# brains.net
KiCad netlist of a schematic drawn in EAGLE
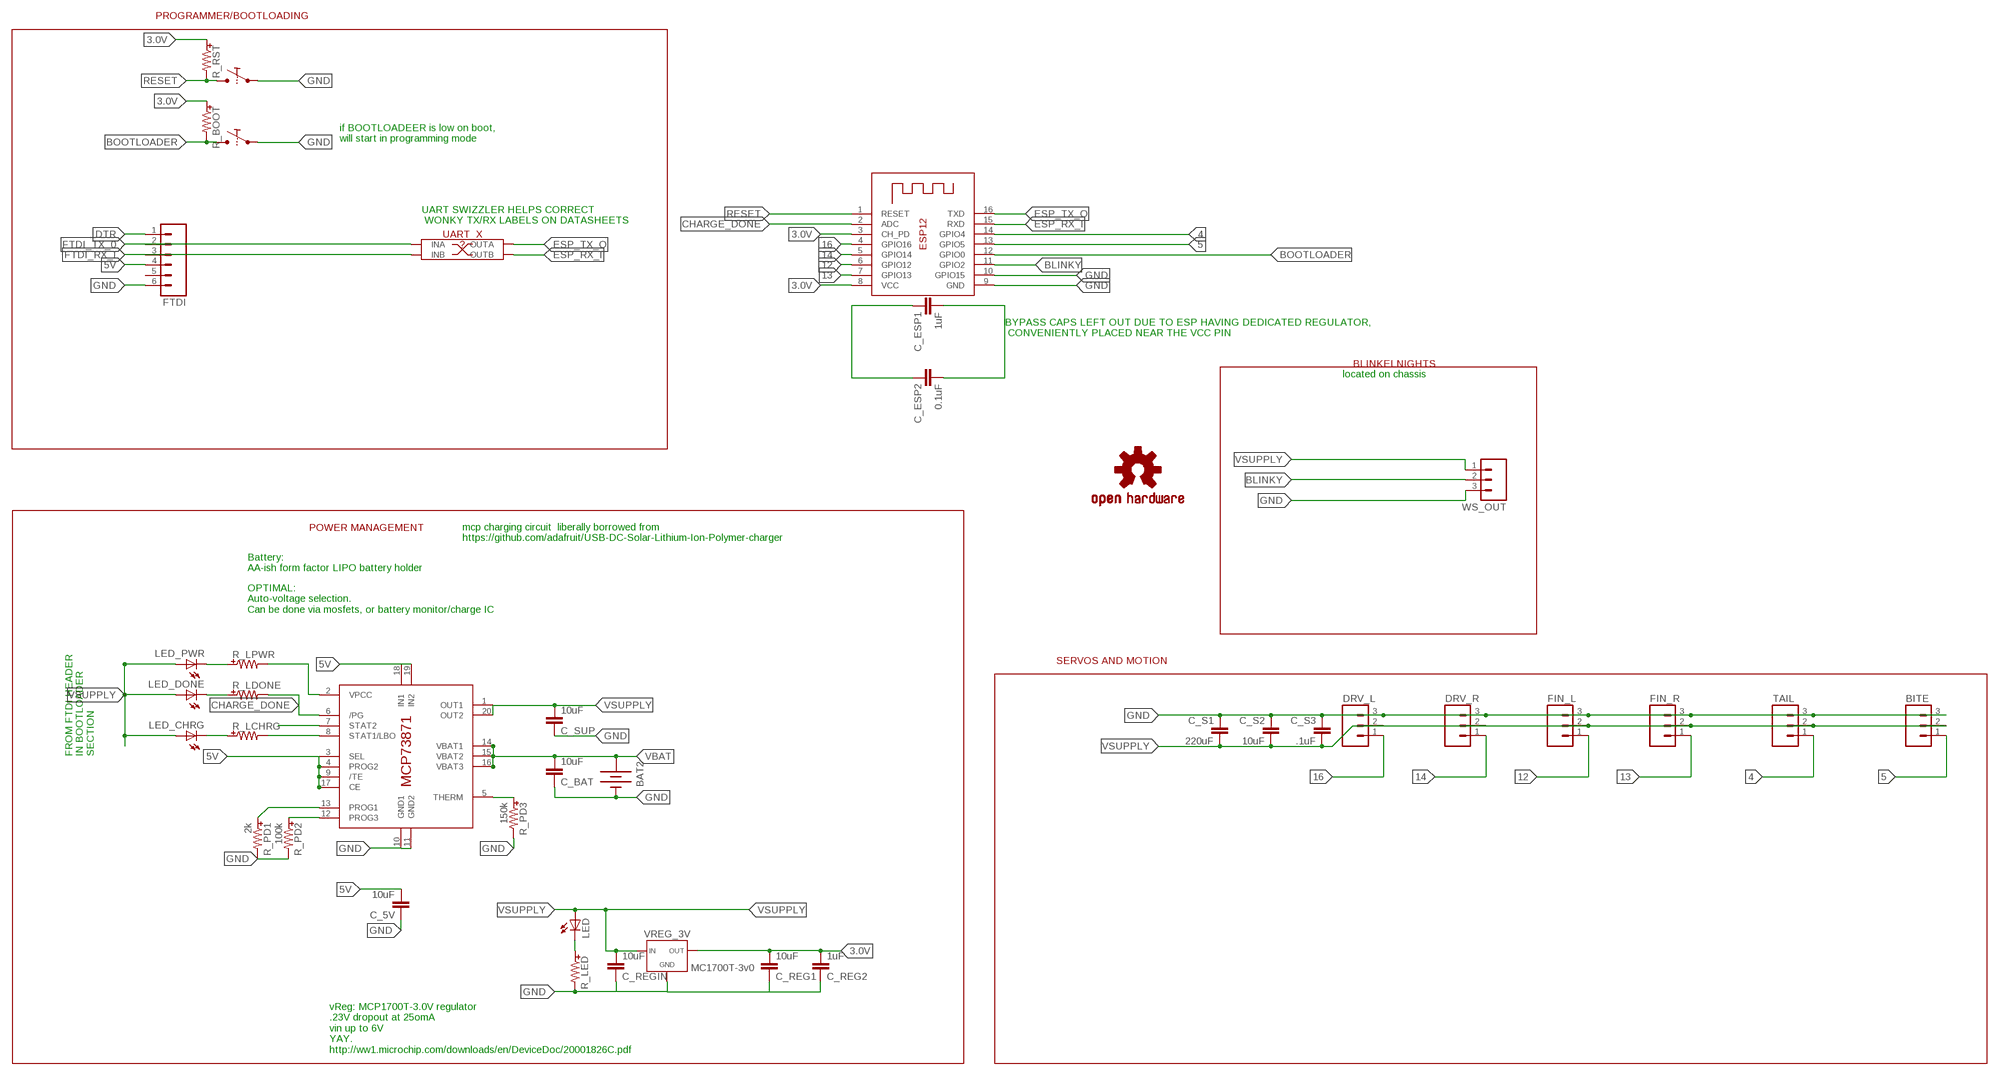
[diagram p0: schematic, sheet 1]

(export (version "E")
  (design (tool "Eeschema 10.0.6"))
  (components
    (comp (ref "BAT2")
      (value "BATTERYAA")
      (footprint "eagle-import:BATTERY-AA")
      (libsource (lib "eagle-import") (part "BATTERYAA"))
    )
    (comp (ref "BITE")
      (value "M03LOCK")
      (footprint "eagle-import:1X03_LOCK")
      (libsource (lib "eagle-import") (part "M03LOCK"))
    )
    (comp (ref "BTN_PROG")
      (value "BUTTONPJRC")
      (footprint "eagle-import:BUTTON-PJRC")
      (libsource (lib "eagle-import") (part "BUTTONPJRC"))
    )
    (comp (ref "BTN_RST")
      (value "BUTTONPJRC")
      (footprint "eagle-import:BUTTON-PJRC")
      (libsource (lib "eagle-import") (part "BUTTONPJRC"))
    )
    (comp (ref "C_5V")
      (value "10uF")
      (footprint "eagle-import:0402-0603-0805-UNIVERSAL")
      (libsource (lib "eagle-import") (part "CAPUNIVERSAL"))
    )
    (comp (ref "C_BAT")
      (value "10uF")
      (footprint "eagle-import:0402-0603-0805-UNIVERSAL")
      (libsource (lib "eagle-import") (part "CAPUNIVERSAL"))
    )
    (comp (ref "C_ESP1")
      (value "1uF")
      (footprint "eagle-import:0402-0603-0805-UNIVERSAL")
      (libsource (lib "eagle-import") (part "CAPUNIVERSAL"))
    )
    (comp (ref "C_ESP2")
      (value "0.1uF")
      (footprint "eagle-import:0402-0603-0805-UNIVERSAL")
      (libsource (lib "eagle-import") (part "CAPUNIVERSAL"))
    )
    (comp (ref "C_REG1")
      (value "10uF")
      (footprint "eagle-import:0402-0603-0805-UNIVERSAL")
      (libsource (lib "eagle-import") (part "CAPUNIVERSAL"))
    )
    (comp (ref "C_REG2")
      (value "1uF")
      (footprint "eagle-import:0402-0603-0805-UNIVERSAL")
      (libsource (lib "eagle-import") (part "CAPUNIVERSAL"))
    )
    (comp (ref "C_REGIN")
      (value "10uF")
      (footprint "eagle-import:0402-0603-0805-UNIVERSAL")
      (libsource (lib "eagle-import") (part "CAPUNIVERSAL"))
    )
    (comp (ref "C_S1")
      (value "220uF")
      (footprint "eagle-import:1210")
      (libsource (lib "eagle-import") (part "CAP1210"))
    )
    (comp (ref "C_S2")
      (value "10uF")
      (footprint "eagle-import:0402-0603-0805-UNIVERSAL")
      (libsource (lib "eagle-import") (part "CAPUNIVERSAL"))
    )
    (comp (ref "C_S3")
      (value ".1uF")
      (footprint "eagle-import:0402-0603-0805-UNIVERSAL")
      (libsource (lib "eagle-import") (part "CAPUNIVERSAL"))
    )
    (comp (ref "C_SUP")
      (value "10uF")
      (footprint "eagle-import:0402-0603-0805-UNIVERSAL")
      (libsource (lib "eagle-import") (part "CAPUNIVERSAL"))
    )
    (comp (ref "DRV_L")
      (value "M03LOCK")
      (footprint "eagle-import:1X03_LOCK")
      (libsource (lib "eagle-import") (part "M03LOCK"))
    )
    (comp (ref "DRV_R")
      (value "M03LOCK")
      (footprint "eagle-import:1X03_LOCK")
      (libsource (lib "eagle-import") (part "M03LOCK"))
    )
    (comp (ref "FIN_L")
      (value "M03LOCK")
      (footprint "eagle-import:1X03_LOCK")
      (libsource (lib "eagle-import") (part "M03LOCK"))
    )
    (comp (ref "FIN_R")
      (value "M03LOCK")
      (footprint "eagle-import:1X03_LOCK")
      (libsource (lib "eagle-import") (part "M03LOCK"))
    )
    (comp (ref "FTDI")
      (value "M06LOCK")
      (footprint "eagle-import:1X06_LOCK")
      (libsource (lib "eagle-import") (part "M06LOCK"))
    )
    (comp (ref "IC_LIPO")
      (value "MCP73871")
      (footprint "eagle-import:QFN20")
      (libsource (lib "eagle-import") (part "MCP73871"))
    )
    (comp (ref "LED")
      (value "LEDUNIVERSAL")
      (footprint "eagle-import:0402-0603-0805-UNIVERSAL")
      (libsource (lib "eagle-import") (part "LEDUNIVERSAL"))
    )
    (comp (ref "LED_CHRG")
      (value "LEDUNIVERSAL")
      (footprint "eagle-import:0402-0603-0805-UNIVERSAL")
      (libsource (lib "eagle-import") (part "LEDUNIVERSAL"))
    )
    (comp (ref "LED_DONE")
      (value "LEDUNIVERSAL")
      (footprint "eagle-import:0402-0603-0805-UNIVERSAL")
      (libsource (lib "eagle-import") (part "LEDUNIVERSAL"))
    )
    (comp (ref "LED_PWR")
      (value "LEDUNIVERSAL")
      (footprint "eagle-import:0402-0603-0805-UNIVERSAL")
      (libsource (lib "eagle-import") (part "LEDUNIVERSAL"))
    )
    (comp (ref "LOGO1")
      (value "OSHW-LOGOS")
      (footprint "eagle-import:OSHW-LOGO-S")
      (libsource (lib "eagle-import") (part "OSHW-LOGOS"))
    )
    (comp (ref "R_BOOT")
      (value "RESISTORUNIVERSAL")
      (footprint "eagle-import:0402-0603-0805-UNIVERSAL")
      (libsource (lib "eagle-import") (part "RESISTORUNIVERSAL"))
    )
    (comp (ref "R_LCHRG")
      (value "RESISTORUNIVERSAL")
      (footprint "eagle-import:0402-0603-0805-UNIVERSAL")
      (libsource (lib "eagle-import") (part "RESISTORUNIVERSAL"))
    )
    (comp (ref "R_LDONE")
      (value "RESISTORUNIVERSAL")
      (footprint "eagle-import:0402-0603-0805-UNIVERSAL")
      (libsource (lib "eagle-import") (part "RESISTORUNIVERSAL"))
    )
    (comp (ref "R_LED")
      (value "RESISTORUNIVERSAL")
      (footprint "eagle-import:0402-0603-0805-UNIVERSAL")
      (libsource (lib "eagle-import") (part "RESISTORUNIVERSAL"))
    )
    (comp (ref "R_LPWR")
      (value "RESISTORUNIVERSAL")
      (footprint "eagle-import:0402-0603-0805-UNIVERSAL")
      (libsource (lib "eagle-import") (part "RESISTORUNIVERSAL"))
    )
    (comp (ref "R_PD1")
      (value "2k")
      (footprint "eagle-import:0402-0603-0805-UNIVERSAL")
      (libsource (lib "eagle-import") (part "RESISTORUNIVERSAL"))
    )
    (comp (ref "R_PD2")
      (value "100k")
      (footprint "eagle-import:0402-0603-0805-UNIVERSAL")
      (libsource (lib "eagle-import") (part "RESISTORUNIVERSAL"))
    )
    (comp (ref "R_PD3")
      (value "150k")
      (footprint "eagle-import:0402-0603-0805-UNIVERSAL")
      (libsource (lib "eagle-import") (part "RESISTORUNIVERSAL"))
    )
    (comp (ref "R_RST")
      (value "RESISTORUNIVERSAL")
      (footprint "eagle-import:0402-0603-0805-UNIVERSAL")
      (libsource (lib "eagle-import") (part "RESISTORUNIVERSAL"))
    )
    (comp (ref "TAIL")
      (value "M03LOCK")
      (footprint "eagle-import:1X03_LOCK")
      (libsource (lib "eagle-import") (part "M03LOCK"))
    )
    (comp (ref "UART_X")
      (value "UART_SWITCHER0603")
      (footprint "eagle-import:UART_SWITCHER_0603")
      (libsource (lib "eagle-import") (part "UART_SWITCHER0603"))
    )
    (comp (ref "VREG_3V")
      (value "MC1700T-3v0")
      (footprint "eagle-import:SOT23")
      (libsource (lib "eagle-import") (part "VOLTAGE-REGULATORMCP1703"))
    )
    (comp (ref "WS_OUT")
      (value "M03LOCK")
      (footprint "eagle-import:1X03_LOCK")
      (libsource (lib "eagle-import") (part "M03LOCK"))
    )
    (comp (ref "X1")
      (value "ESP-12")
      (footprint "eagle-import:ESP-12")
      (libsource (lib "eagle-import") (part "ESP-12"))
    )
  )
  (nets
    (net (code "1") (name "3.0V") (class "Default")
      (node (ref "C_REG1") (pin "+") (pinfunction "2_+") (pintype "passive"))
      (node (ref "C_REG2") (pin "+") (pinfunction "2_+") (pintype "passive"))
      (node (ref "R_BOOT") (pin "+") (pinfunction "1_+") (pintype "passive"))
      (node (ref "R_RST") (pin "+") (pinfunction "1_+") (pintype "passive"))
      (node (ref "VREG_3V") (pin "2") (pinfunction "OUT_2") (pintype "input"))
      (node (ref "X1") (pin "3") (pinfunction "CH_PD_3") (pintype "input"))
      (node (ref "X1") (pin "8") (pinfunction "VCC_8") (pintype "power_in"))
    )
    (net (code "2") (name "4") (class "Default")
      (node (ref "TAIL") (pin "1") (pinfunction "1_1") (pintype "passive"))
      (node (ref "X1") (pin "14") (pinfunction "GPIO4_14") (pintype "bidirectional"))
    )
    (net (code "3") (name "5") (class "Default")
      (node (ref "BITE") (pin "1") (pinfunction "1_1") (pintype "passive"))
      (node (ref "X1") (pin "13") (pinfunction "GPIO5_13") (pintype "bidirectional"))
    )
    (net (code "4") (name "5V") (class "Default")
      (node (ref "C_5V") (pin "+") (pinfunction "2_+") (pintype "passive"))
      (node (ref "FTDI") (pin "4") (pinfunction "4_4") (pintype "passive"))
      (node (ref "IC_LIPO") (pin "17") (pinfunction "CE_17") (pintype "input"))
      (node (ref "IC_LIPO") (pin "18") (pinfunction "IN1_18") (pintype "input"))
      (node (ref "IC_LIPO") (pin "19") (pinfunction "IN2_19") (pintype "input"))
      (node (ref "IC_LIPO") (pin "3") (pinfunction "SEL_3") (pintype "input"))
      (node (ref "IC_LIPO") (pin "4") (pinfunction "PROG2_4") (pintype "input"))
      (node (ref "IC_LIPO") (pin "9") (pinfunction "/TE_9") (pintype "input"))
    )
    (net (code "5") (name "12") (class "Default")
      (node (ref "FIN_L") (pin "1") (pinfunction "1_1") (pintype "passive"))
      (node (ref "X1") (pin "6") (pinfunction "GPIO12_6") (pintype "bidirectional"))
    )
    (net (code "6") (name "13") (class "Default")
      (node (ref "FIN_R") (pin "1") (pinfunction "1_1") (pintype "passive"))
      (node (ref "X1") (pin "7") (pinfunction "GPIO13_7") (pintype "bidirectional"))
    )
    (net (code "7") (name "14") (class "Default")
      (node (ref "DRV_R") (pin "1") (pinfunction "1_1") (pintype "passive"))
      (node (ref "X1") (pin "5") (pinfunction "GPIO14_5") (pintype "bidirectional"))
    )
    (net (code "8") (name "16") (class "Default")
      (node (ref "DRV_L") (pin "1") (pinfunction "1_1") (pintype "passive"))
      (node (ref "X1") (pin "4") (pinfunction "GPIO16_4") (pintype "bidirectional"))
    )
    (net (code "9") (name "BLINKY") (class "Default")
      (node (ref "WS_OUT") (pin "2") (pinfunction "2_2") (pintype "passive"))
      (node (ref "X1") (pin "11") (pinfunction "GPIO2_11") (pintype "bidirectional"))
    )
    (net (code "10") (name "BOOTLOADER") (class "Default")
      (node (ref "BTN_PROG") (pin "A1") (pinfunction "P$1_A1") (pintype "bidirectional"))
      (node (ref "BTN_PROG") (pin "A2") (pinfunction "P$1_A2") (pintype "bidirectional"))
      (node (ref "R_BOOT") (pin "-") (pinfunction "2_-") (pintype "passive"))
      (node (ref "X1") (pin "12") (pinfunction "GPIO0_12") (pintype "bidirectional"))
    )
    (net (code "11") (name "CHARGE_DONE") (class "Default")
      (node (ref "IC_LIPO") (pin "6") (pinfunction "/PG_6") (pintype "output"))
      (node (ref "R_LDONE") (pin "-") (pinfunction "2_-") (pintype "passive"))
      (node (ref "X1") (pin "2") (pinfunction "ADC_2") (pintype "passive"))
    )
    (net (code "12") (name "DTR") (class "Default")
      (node (ref "FTDI") (pin "1") (pinfunction "1_1") (pintype "passive"))
    )
    (net (code "13") (name "ESP_RX_I") (class "Default")
      (node (ref "UART_X") (pin "TX_B") (pinfunction "OUTB_TX_B") (pintype "bidirectional"))
      (node (ref "X1") (pin "15") (pinfunction "RXD_15") (pintype "input"))
    )
    (net (code "14") (name "ESP_TX_O") (class "Default")
      (node (ref "UART_X") (pin "RX_B") (pinfunction "OUTA_RX_B") (pintype "bidirectional"))
      (node (ref "X1") (pin "16") (pinfunction "TXD_16") (pintype "output"))
    )
    (net (code "15") (name "FTDI_RX_I") (class "Default")
      (node (ref "FTDI") (pin "3") (pinfunction "3_3") (pintype "passive"))
      (node (ref "UART_X") (pin "RX_A") (pinfunction "INB_RX_A") (pintype "bidirectional"))
    )
    (net (code "16") (name "FTDI_TX_0") (class "Default")
      (node (ref "FTDI") (pin "2") (pinfunction "2_2") (pintype "passive"))
      (node (ref "UART_X") (pin "TX_A") (pinfunction "INA_TX_A") (pintype "bidirectional"))
    )
    (net (code "17") (name "GND") (class "Default")
      (node (ref "BAT2") (pin "GND@1") (pinfunction "-_GND@1") (pintype "power_in"))
      (node (ref "BITE") (pin "3") (pinfunction "3_3") (pintype "passive"))
      (node (ref "BTN_PROG") (pin "B1") (pinfunction "P$2_B1") (pintype "bidirectional"))
      (node (ref "BTN_PROG") (pin "B2") (pinfunction "P$2_B2") (pintype "bidirectional"))
      (node (ref "BTN_RST") (pin "B1") (pinfunction "P$2_B1") (pintype "bidirectional"))
      (node (ref "BTN_RST") (pin "B2") (pinfunction "P$2_B2") (pintype "bidirectional"))
      (node (ref "C_5V") (pin "-") (pinfunction "1_-") (pintype "passive"))
      (node (ref "C_BAT") (pin "-") (pinfunction "1_-") (pintype "passive"))
      (node (ref "C_REG1") (pin "-") (pinfunction "1_-") (pintype "passive"))
      (node (ref "C_REG2") (pin "-") (pinfunction "1_-") (pintype "passive"))
      (node (ref "C_REGIN") (pin "-") (pinfunction "1_-") (pintype "passive"))
      (node (ref "C_S1") (pin "1") (pinfunction "1_1") (pintype "passive"))
      (node (ref "C_S2") (pin "-") (pinfunction "1_-") (pintype "passive"))
      (node (ref "C_S3") (pin "-") (pinfunction "1_-") (pintype "passive"))
      (node (ref "C_SUP") (pin "-") (pinfunction "1_-") (pintype "passive"))
      (node (ref "DRV_L") (pin "3") (pinfunction "3_3") (pintype "passive"))
      (node (ref "DRV_R") (pin "3") (pinfunction "3_3") (pintype "passive"))
      (node (ref "FIN_L") (pin "3") (pinfunction "3_3") (pintype "passive"))
      (node (ref "FIN_R") (pin "3") (pinfunction "3_3") (pintype "passive"))
      (node (ref "FTDI") (pin "6") (pinfunction "6_6") (pintype "passive"))
      (node (ref "IC_LIPO") (pin "10") (pinfunction "GND1_10") (pintype "power_in"))
      (node (ref "IC_LIPO") (pin "11") (pinfunction "GND2_11") (pintype "power_in"))
      (node (ref "R_LED") (pin "-") (pinfunction "2_-") (pintype "passive"))
      (node (ref "R_PD1") (pin "-") (pinfunction "2_-") (pintype "passive"))
      (node (ref "R_PD2") (pin "-") (pinfunction "2_-") (pintype "passive"))
      (node (ref "R_PD3") (pin "-") (pinfunction "2_-") (pintype "passive"))
      (node (ref "TAIL") (pin "3") (pinfunction "3_3") (pintype "passive"))
      (node (ref "VREG_3V") (pin "1") (pinfunction "GND_1") (pintype "input"))
      (node (ref "WS_OUT") (pin "3") (pinfunction "3_3") (pintype "passive"))
      (node (ref "X1") (pin "10") (pinfunction "GPIO15_10") (pintype "bidirectional"))
      (node (ref "X1") (pin "9") (pinfunction "GND_9") (pintype "power_in"))
    )
    (net (code "18") (name "Net-(C_ESP1-1)") (class "Default")
      (node (ref "C_ESP1") (pin "-") (pinfunction "1_-") (pintype "passive"))
      (node (ref "C_ESP2") (pin "-") (pinfunction "1_-") (pintype "passive"))
    )
    (net (code "19") (name "Net-(C_ESP1-2)") (class "Default")
      (node (ref "C_ESP1") (pin "+") (pinfunction "2_+") (pintype "passive"))
      (node (ref "C_ESP2") (pin "+") (pinfunction "2_+") (pintype "passive"))
    )
    (net (code "20") (name "Net-(IC_LIPO-PROG1)") (class "Default")
      (node (ref "IC_LIPO") (pin "13") (pinfunction "PROG1_13") (pintype "input"))
      (node (ref "R_PD1") (pin "+") (pinfunction "1_+") (pintype "passive"))
    )
    (net (code "21") (name "Net-(IC_LIPO-PROG3)") (class "Default")
      (node (ref "IC_LIPO") (pin "12") (pinfunction "PROG3_12") (pintype "input"))
      (node (ref "R_PD2") (pin "+") (pinfunction "1_+") (pintype "passive"))
    )
    (net (code "22") (name "Net-(IC_LIPO-STAT1{slash}LBO)") (class "Default")
      (node (ref "IC_LIPO") (pin "8") (pinfunction "STAT1/LBO_8") (pintype "output"))
      (node (ref "R_LCHRG") (pin "-") (pinfunction "2_-") (pintype "passive"))
    )
    (net (code "23") (name "Net-(IC_LIPO-THERM)") (class "Default")
      (node (ref "IC_LIPO") (pin "5") (pinfunction "THERM_5") (pintype "input"))
      (node (ref "R_PD3") (pin "+") (pinfunction "1_+") (pintype "passive"))
    )
    (net (code "24") (name "Net-(IC_LIPO-VPCC)") (class "Default")
      (node (ref "IC_LIPO") (pin "2") (pinfunction "VPCC_2") (pintype "input"))
      (node (ref "R_LPWR") (pin "-") (pinfunction "2_-") (pintype "passive"))
    )
    (net (code "25") (name "Net-(LED-C)") (class "Default")
      (node (ref "LED") (pin "-") (pinfunction "C_-") (pintype "passive"))
      (node (ref "R_LED") (pin "+") (pinfunction "1_+") (pintype "passive"))
    )
    (net (code "26") (name "Net-(LED_CHRG-C)") (class "Default")
      (node (ref "LED_CHRG") (pin "-") (pinfunction "C_-") (pintype "passive"))
      (node (ref "R_LCHRG") (pin "+") (pinfunction "1_+") (pintype "passive"))
    )
    (net (code "27") (name "Net-(LED_DONE-C)") (class "Default")
      (node (ref "LED_DONE") (pin "-") (pinfunction "C_-") (pintype "passive"))
      (node (ref "R_LDONE") (pin "+") (pinfunction "1_+") (pintype "passive"))
    )
    (net (code "28") (name "Net-(LED_PWR-C)") (class "Default")
      (node (ref "LED_PWR") (pin "-") (pinfunction "C_-") (pintype "passive"))
      (node (ref "R_LPWR") (pin "+") (pinfunction "1_+") (pintype "passive"))
    )
    (net (code "29") (name "RESET") (class "Default")
      (node (ref "BTN_RST") (pin "A1") (pinfunction "P$1_A1") (pintype "bidirectional"))
      (node (ref "BTN_RST") (pin "A2") (pinfunction "P$1_A2") (pintype "bidirectional"))
      (node (ref "R_RST") (pin "-") (pinfunction "2_-") (pintype "passive"))
      (node (ref "X1") (pin "1") (pinfunction "RESET_1") (pintype "input"))
    )
    (net (code "30") (name "VBAT") (class "Default")
      (node (ref "BAT2") (pin "PWR@1") (pinfunction "+_PWR@1") (pintype "power_in"))
      (node (ref "C_BAT") (pin "+") (pinfunction "2_+") (pintype "passive"))
      (node (ref "IC_LIPO") (pin "14") (pinfunction "VBAT1_14") (pintype "output"))
      (node (ref "IC_LIPO") (pin "15") (pinfunction "VBAT2_15") (pintype "output"))
      (node (ref "IC_LIPO") (pin "16") (pinfunction "VBAT3_16") (pintype "output"))
    )
    (net (code "31") (name "VSUPPLY") (class "Default")
      (node (ref "BITE") (pin "2") (pinfunction "2_2") (pintype "passive"))
      (node (ref "C_REGIN") (pin "+") (pinfunction "2_+") (pintype "passive"))
      (node (ref "C_S1") (pin "2") (pinfunction "2_2") (pintype "passive"))
      (node (ref "C_S2") (pin "+") (pinfunction "2_+") (pintype "passive"))
      (node (ref "C_S3") (pin "+") (pinfunction "2_+") (pintype "passive"))
      (node (ref "C_SUP") (pin "+") (pinfunction "2_+") (pintype "passive"))
      (node (ref "DRV_L") (pin "2") (pinfunction "2_2") (pintype "passive"))
      (node (ref "DRV_R") (pin "2") (pinfunction "2_2") (pintype "passive"))
      (node (ref "FIN_L") (pin "2") (pinfunction "2_2") (pintype "passive"))
      (node (ref "FIN_R") (pin "2") (pinfunction "2_2") (pintype "passive"))
      (node (ref "IC_LIPO") (pin "1") (pinfunction "OUT1_1") (pintype "output"))
      (node (ref "IC_LIPO") (pin "20") (pinfunction "OUT2_20") (pintype "output"))
      (node (ref "LED") (pin "+") (pinfunction "A_+") (pintype "passive"))
      (node (ref "LED_CHRG") (pin "+") (pinfunction "A_+") (pintype "passive"))
      (node (ref "LED_DONE") (pin "+") (pinfunction "A_+") (pintype "passive"))
      (node (ref "LED_PWR") (pin "+") (pinfunction "A_+") (pintype "passive"))
      (node (ref "TAIL") (pin "2") (pinfunction "2_2") (pintype "passive"))
      (node (ref "VREG_3V") (pin "3") (pinfunction "IN_3") (pintype "input"))
      (node (ref "WS_OUT") (pin "1") (pinfunction "1_1") (pintype "passive"))
    )
    (net (code "32") (name "unconnected-(FTDI-Pad5)") (class "Default")
      (node (ref "FTDI") (pin "5") (pinfunction "5_5") (pintype "passive"))
    )
    (net (code "33") (name "unconnected-(IC_LIPO-STAT2-Pad7)") (class "Default")
      (node (ref "IC_LIPO") (pin "7") (pinfunction "STAT2_7") (pintype "output"))
    )
  )
)
